# FUSE_AND_I_SENSE.net
KiCad netlist of a schematic drawn in Altium Designer
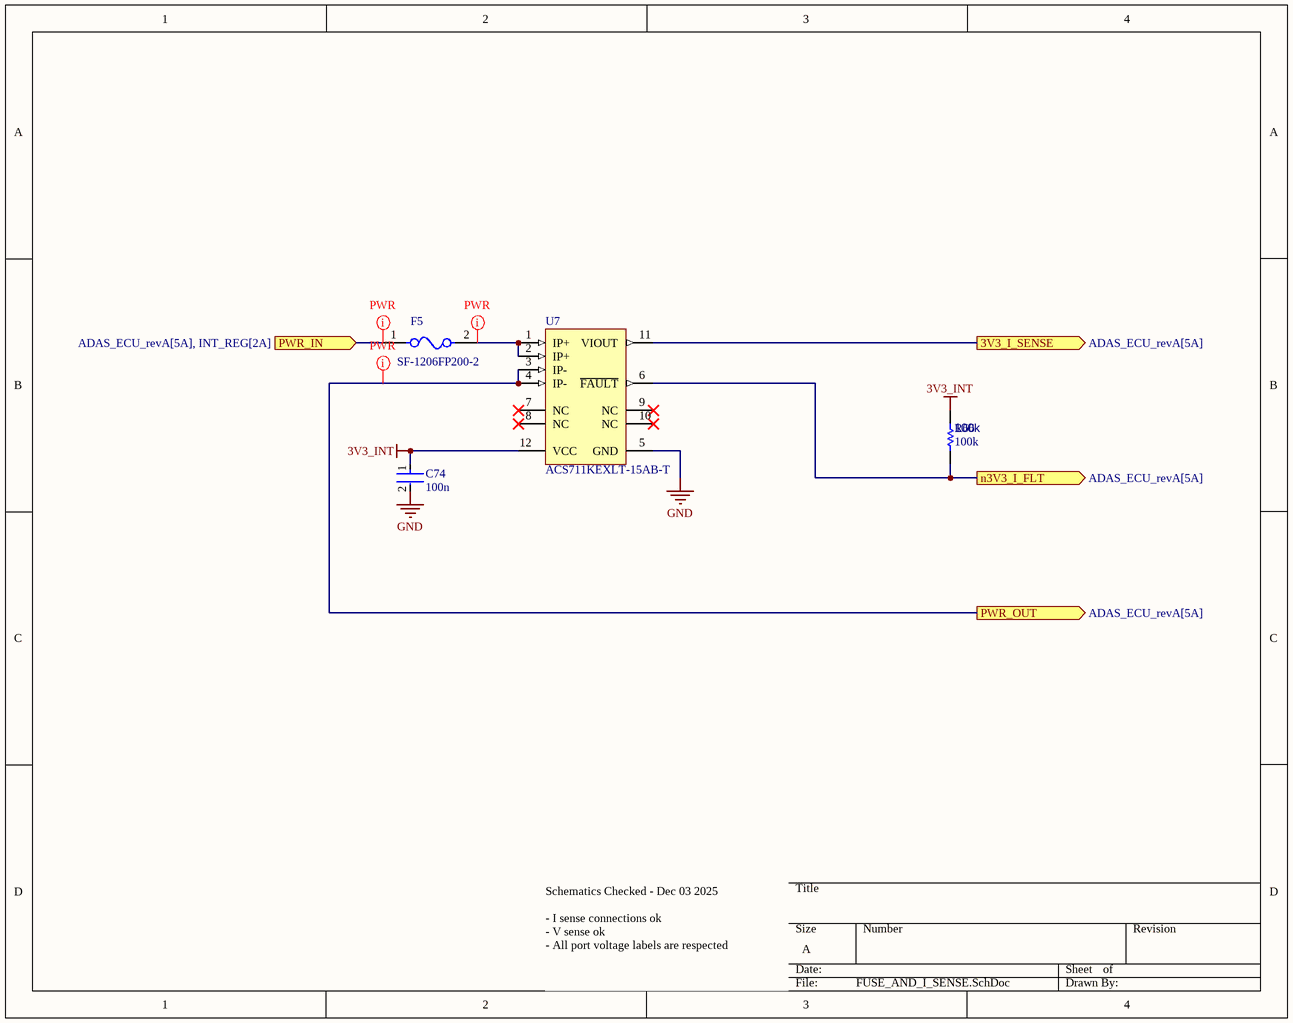
[diagram p0: FUSE_AND_I_SENSE.SchDoc]

(export (version "E")
  (design (tool "Eeschema 10.0.6"))
  (components
    (comp (ref "C74")
      (value "100n")
      (footprint "FP-0402-L_1_0_0_05-W_0_5-IPC_A")
      (description "LARGE PADS, 0402 CAP, CHANGE COMMENT TO MATCH REAL P/N")
      (libsource (lib "Space Concordia") (part "b4654b650e69147ec39a6b967a45e02"))
    )
    (comp (ref "F5")
      (value "SF-1206FP200-2")
      (footprint "FP-SF-1206FP-MFG")
      (description "FUSE BOARD MOUNT 2A 63VDC 1206")
      (libsource (lib "Altium Content Vault") (part "5bcf9b9f640e542cf0359d10258e979"))
    )
    (comp (ref "R66")
      (value "100k")
      (footprint "R0603B")
      (description "Resistor")
      (fields (field (name "ALTIUM_VALUE") "100k"))
      (libsource (lib "Space Concordia") (part "Resistor"))
    )
    (comp (ref "U7")
      (value "ACS711KEXLT-15AB-T")
      (footprint "ALEG-EX-12_V")
      (libsource (lib "Altium Content Vault") (part "ALEG-ACS711-QFN-12"))
    )
  )
  (nets
    (net (code "1") (name "/3V3_I_SENSE") (class "Default")
      (node (ref "U7") (pin "11") (pinfunction "VIOUT_11") (pintype "output"))
    )
    (net (code "2") (name "/PWR_IN") (class "Default")
      (node (ref "F5") (pin "1") (pinfunction "1_1") (pintype "passive"))
    )
    (net (code "3") (name "/PWR_OUT") (class "Default")
      (node (ref "U7") (pin "3") (pinfunction "IP-_3") (pintype "input"))
      (node (ref "U7") (pin "4") (pinfunction "IP-_4") (pintype "input"))
    )
    (net (code "4") (name "/n3V3_I_FLT") (class "Default")
      (node (ref "R66") (pin "1") (pinfunction "1_1") (pintype "passive"))
      (node (ref "U7") (pin "6") (pinfunction "~{FAULT}_6") (pintype "output"))
    )
    (net (code "5") (name "3V3_INT") (class "Default")
      (node (ref "C74") (pin "1") (pinfunction "1_1") (pintype "passive"))
      (node (ref "R66") (pin "2") (pinfunction "2_2") (pintype "passive"))
      (node (ref "U7") (pin "12") (pinfunction "VCC_12") (pintype "power_in"))
    )
    (net (code "6") (name "GND") (class "Default")
      (node (ref "C74") (pin "2") (pinfunction "2_2") (pintype "passive"))
      (node (ref "U7") (pin "5") (pinfunction "GND_5") (pintype "power_in"))
    )
    (net (code "7") (name "Net-(F5-Pad2)") (class "Default")
      (node (ref "F5") (pin "2") (pinfunction "2_2") (pintype "passive"))
      (node (ref "U7") (pin "1") (pinfunction "IP+_1") (pintype "input"))
      (node (ref "U7") (pin "2") (pinfunction "IP+_2") (pintype "input"))
    )
    (net (code "8") (name "unconnected-(U7-NC-Pad7)") (class "Default")
      (node (ref "U7") (pin "7") (pinfunction "NC_7") (pintype "passive+no_connect"))
    )
    (net (code "9") (name "unconnected-(U7-NC-Pad8)") (class "Default")
      (node (ref "U7") (pin "8") (pinfunction "NC_8") (pintype "passive+no_connect"))
    )
    (net (code "10") (name "unconnected-(U7-NC-Pad9)") (class "Default")
      (node (ref "U7") (pin "9") (pinfunction "NC_9") (pintype "passive+no_connect"))
    )
    (net (code "11") (name "unconnected-(U7-NC-Pad10)") (class "Default")
      (node (ref "U7") (pin "10") (pinfunction "NC_10") (pintype "passive+no_connect"))
    )
  )
)
